# Connector_SOM240_1.net
KiCad netlist of a schematic drawn in Altium Designer
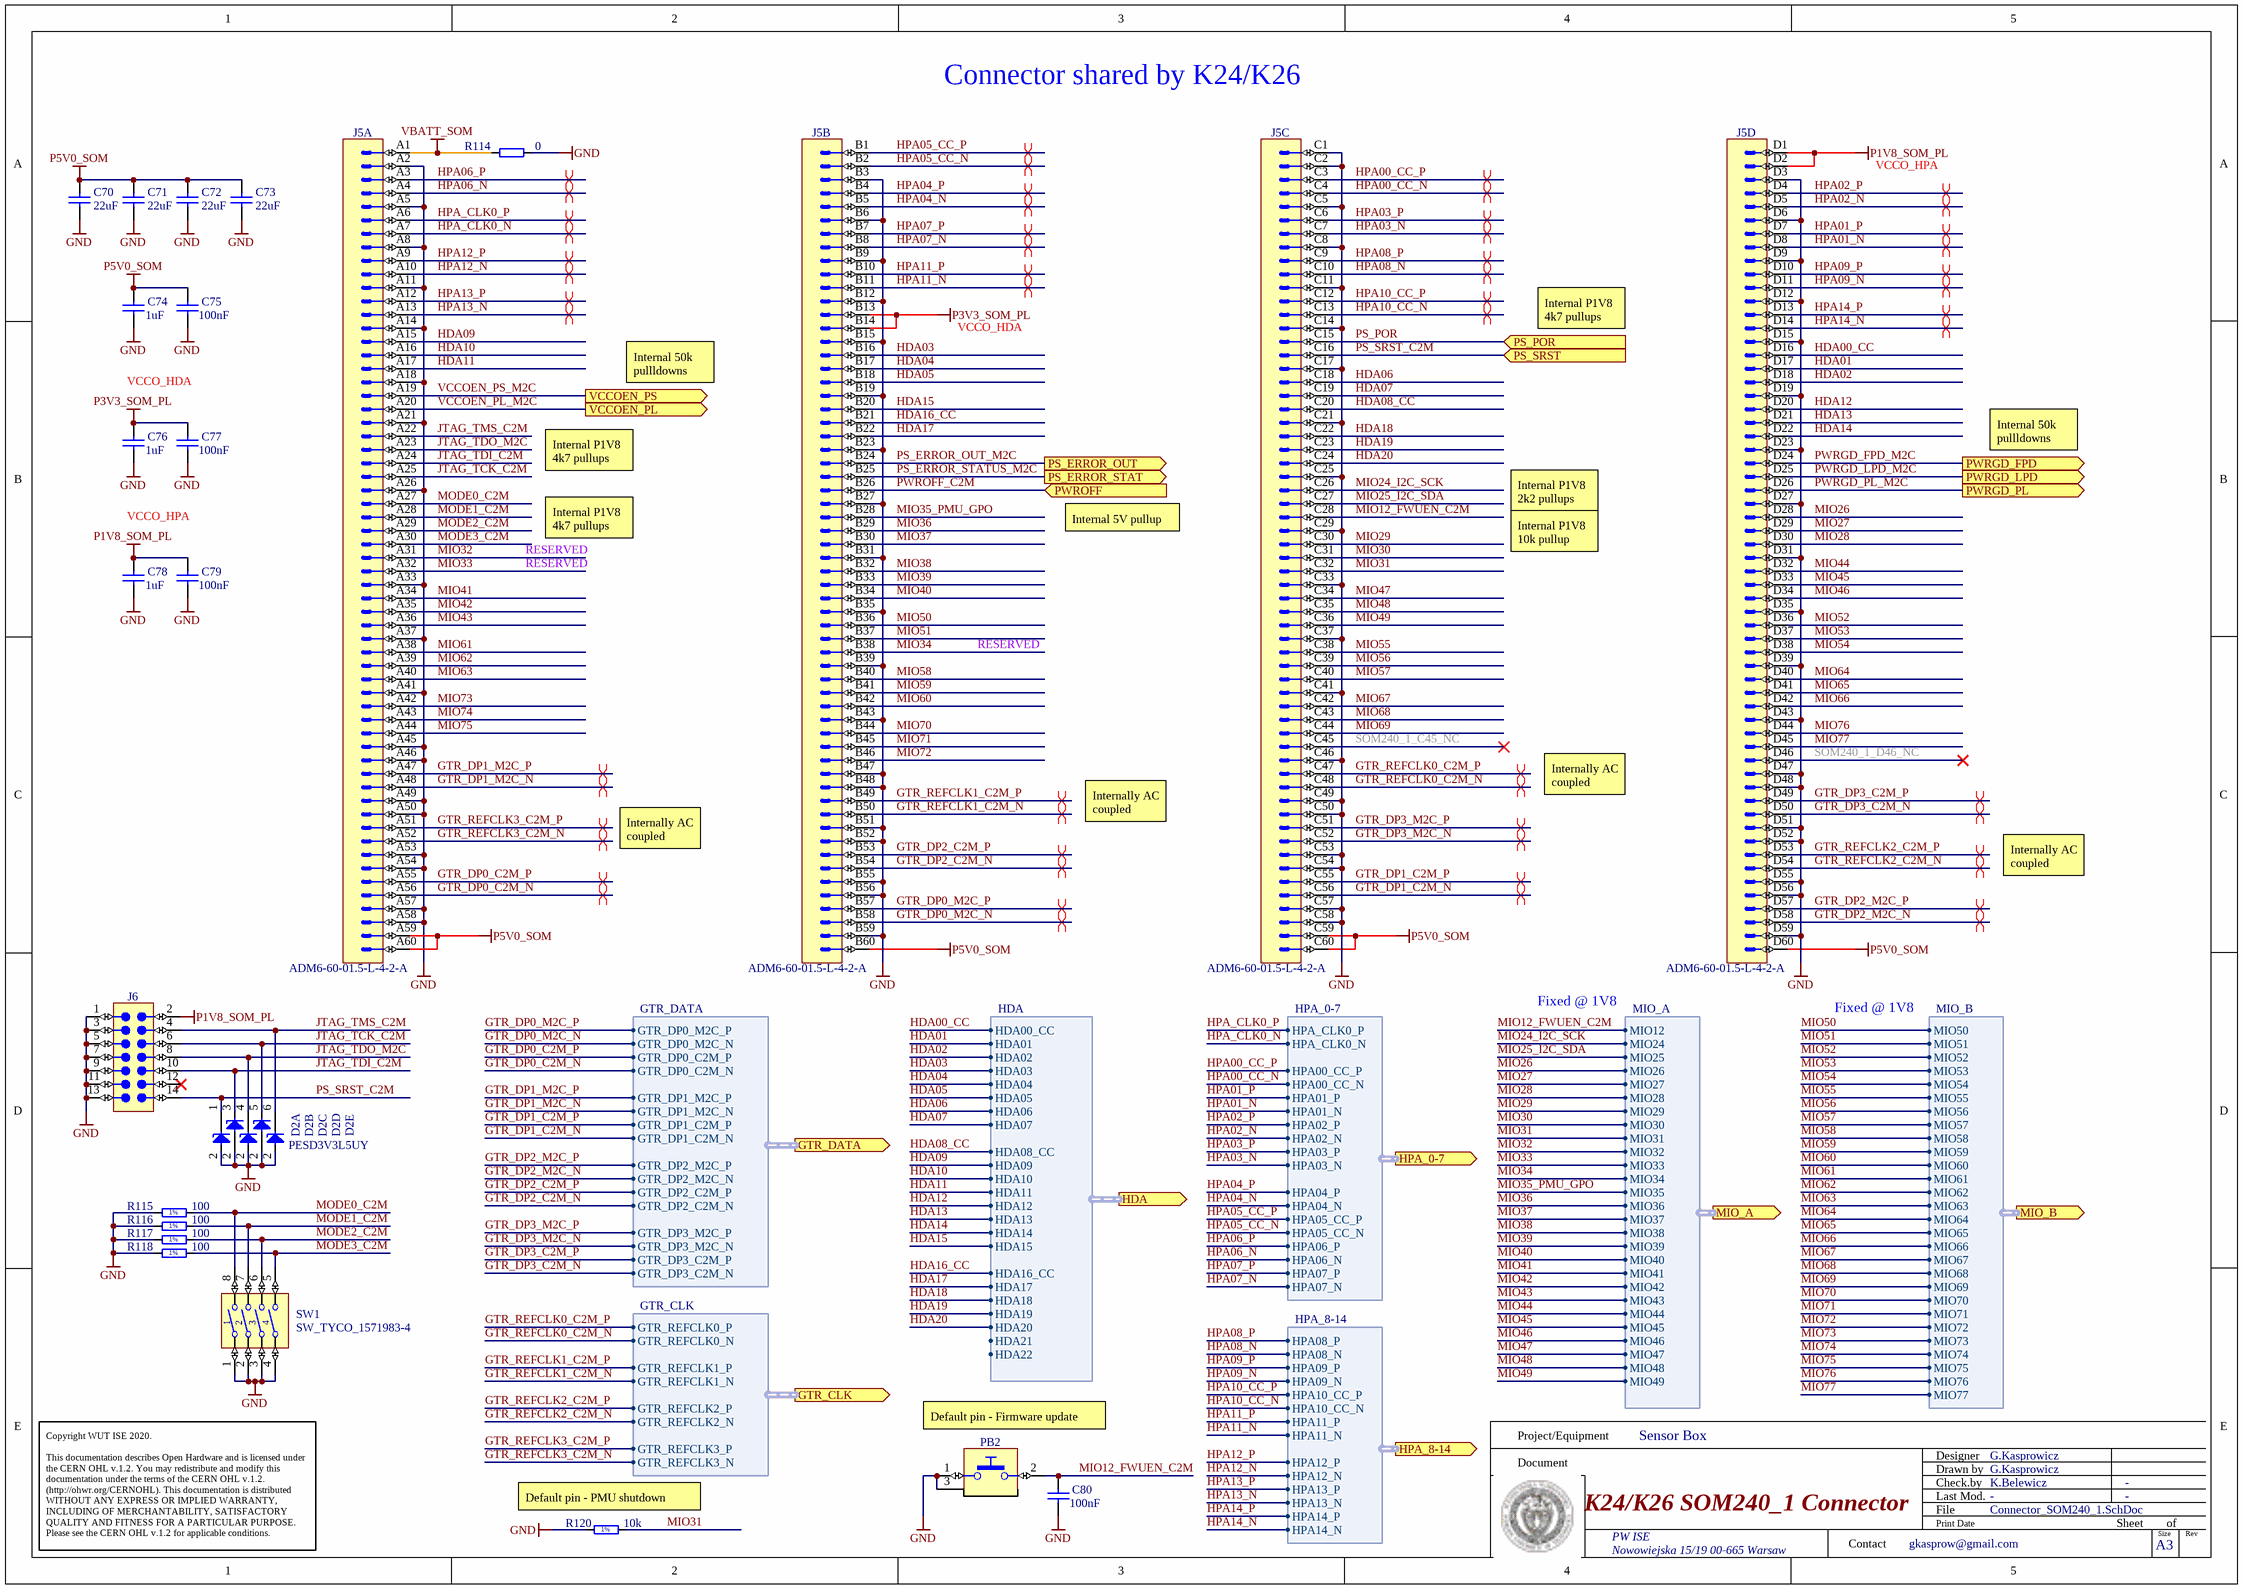
[diagram p0: Connector_SOM240_1.SchDoc]

(export (version "E")
  (design (tool "Eeschema 10.0.6"))
  (components
    (comp (ref "C70")
      (value "22uF")
      (footprint "CAPC2012X135N")
      (description "Non-polarised capacitor")
      (fields
        (field (name "PART NUMBER") "CC0805_22UF_16V_10%_X5R")
        (field (name "VOLTAGE") "16V")
        (field (name "AUTHOR") "CERN DEM JLC")
      )
      (libsource (lib "Capacitors") (part "Capacitor - non polarized"))
    )
    (comp (ref "C71")
      (value "22uF")
      (footprint "CAPC2012X135N")
      (description "Non-polarised capacitor")
      (fields
        (field (name "PART NUMBER") "CC0805_22UF_16V_10%_X5R")
        (field (name "VOLTAGE") "16V")
        (field (name "AUTHOR") "CERN DEM JLC")
      )
      (libsource (lib "Capacitors") (part "Capacitor - non polarized"))
    )
    (comp (ref "C72")
      (value "22uF")
      (footprint "CAPC2012X135N")
      (description "Non-polarised capacitor")
      (fields
        (field (name "PART NUMBER") "CC0805_22UF_16V_10%_X5R")
        (field (name "VOLTAGE") "16V")
        (field (name "AUTHOR") "CERN DEM JLC")
      )
      (libsource (lib "Capacitors") (part "Capacitor - non polarized"))
    )
    (comp (ref "C73")
      (value "22uF")
      (footprint "CAPC2012X135N")
      (description "Non-polarised capacitor")
      (fields
        (field (name "PART NUMBER") "CC0805_22UF_16V_10%_X5R")
        (field (name "VOLTAGE") "16V")
        (field (name "AUTHOR") "CERN DEM JLC")
      )
      (libsource (lib "Capacitors") (part "Capacitor - non polarized"))
    )
    (comp (ref "C74")
      (value "1uF")
      (footprint "CAPC1005X55N")
      (description "Non-polarised capacitor")
      (fields
        (field (name "PART NUMBER") "CC0402_1UF_16V_10%_X5R")
        (field (name "VOLTAGE") "16V")
        (field (name "AUTHOR") "CERN DEM JLC")
      )
      (libsource (lib "Capacitors") (part "Capacitor - non polarized"))
    )
    (comp (ref "C75")
      (value "100nF")
      (footprint "CAPC1005X55N")
      (description "Non-polarised capacitor")
      (fields
        (field (name "PART NUMBER") "CC0402_100NF_16V_10%_X5R")
        (field (name "VOLTAGE") "16V")
        (field (name "AUTHOR") "CERN DEM JLC")
      )
      (libsource (lib "Capacitors") (part "Capacitor - non polarized"))
    )
    (comp (ref "C76")
      (value "1uF")
      (footprint "CAPC1005X55N")
      (description "Non-polarised capacitor")
      (fields
        (field (name "PART NUMBER") "CC0402_1UF_16V_10%_X5R")
        (field (name "VOLTAGE") "16V")
        (field (name "AUTHOR") "CERN DEM JLC")
      )
      (libsource (lib "Capacitors") (part "Capacitor - non polarized"))
    )
    (comp (ref "C77")
      (value "100nF")
      (footprint "CAPC1005X55N")
      (description "Non-polarised capacitor")
      (fields
        (field (name "PART NUMBER") "CC0402_100NF_16V_10%_X5R")
        (field (name "VOLTAGE") "16V")
        (field (name "AUTHOR") "CERN DEM JLC")
      )
      (libsource (lib "Capacitors") (part "Capacitor - non polarized"))
    )
    (comp (ref "C78")
      (value "1uF")
      (footprint "CAPC1005X55N")
      (description "Non-polarised capacitor")
      (fields
        (field (name "PART NUMBER") "CC0402_1UF_16V_10%_X5R")
        (field (name "VOLTAGE") "16V")
        (field (name "AUTHOR") "CERN DEM JLC")
      )
      (libsource (lib "Capacitors") (part "Capacitor - non polarized"))
    )
    (comp (ref "C79")
      (value "100nF")
      (footprint "CAPC1005X55N")
      (description "Non-polarised capacitor")
      (fields
        (field (name "PART NUMBER") "CC0402_100NF_16V_10%_X5R")
        (field (name "VOLTAGE") "16V")
        (field (name "AUTHOR") "CERN DEM JLC")
      )
      (libsource (lib "Capacitors") (part "Capacitor - non polarized"))
    )
    (comp (ref "C80")
      (value "100nF")
      (footprint "CAPC1005X55N")
      (description "Non-polarised capacitor")
      (fields
        (field (name "PART NUMBER") "CC0402_100NF_16V_10%_X5R")
        (field (name "VOLTAGE") "16V")
        (field (name "AUTHOR") "CERN DEM JLC")
      )
      (libsource (lib "Capacitors") (part "Capacitor - non polarized"))
    )
    (comp (ref "D2")
      (value "PESD3V3L5UY")
      (footprint "SOT65P210X110-6N")
      (description "Fivefold ESD Protection Diode Arrays")
      (fields
        (field (name "VOLTAGE") "3.3V")
        (field (name "POWER") "200W")
        (field (name "AUTHOR") "CERN DEM WB")
      )
      (libsource (lib "") (part "PESD Array 5diodes 6pins Common anode2_4"))
    )
    (comp (ref "J5")
      (value "Header 240")
      (footprint "SAMTEC_ADM6-60-01.5-L-4-2-A")
      (description "Connector 240 Male contacts in 4 row abcd")
      (fields
        (field (name "PART NUMBER") "SAMTEC_ADM6-60-01.5-L-4-2-A")
        (field (name "MANUFACTURER") "SAMTEC")
        (field (name "MANUFACTURER PART NUMBER") "ADM6-60-01.5-L-4-2-A")
        (field (name "AUTHOR") "CERN DEM HF")
      )
      (libsource (lib "Connectors") (part "Connector 240 Male (4x60) (abcd)"))
    )
    (comp (ref "J6")
      (value "~")
      (footprint "MOLEX_87832-1420")
      (description "Connector 14 Male")
      (fields
        (field (name "PART NUMBER") "MOLEX_87832-1420")
        (field (name "MANUFACTURER") "MOLEX")
        (field (name "AUTHOR") "CERN DEM JLC")
      )
      (libsource (lib "Connectors") (part "Connector 14 Male"))
    )
    (comp (ref "PB2")
      (value "~")
      (footprint "PB_OMRON_B3U-1100P")
      (description "Push-Button Switch SPDT")
      (fields
        (field (name "PART NUMBER") "PB_OMRON_B3U-1100P")
        (field (name "MANUFACTURER") "OMRON")
        (field (name "AUTHOR") "CERN DEM JLC")
      )
      (libsource (lib "Eletro-mechanical") (part "PB SPST 1NO-2NO 3CASE"))
    )
    (comp (ref "R114")
      (value "0")
      (footprint "RESC1005X40N")
      (description "Resistor")
      (fields
        (field (name "PART NUMBER") "R0402_0R_JUMPER")
        (field (name "MANUFACTURER") "GENERIC")
        (field (name "AUTHOR") "CERN DEM JLC")
      )
      (libsource (lib "Resistors") (part "Resistor"))
    )
    (comp (ref "R115")
      (value "100")
      (footprint "RESC1005X40N")
      (description "Resistor - 1%")
      (fields
        (field (name "PART NUMBER") "R0402_100R_1%_0.0625W_100PPM")
        (field (name "POWER") "0.0625W")
        (field (name "AUTHOR") "CERN DEM JLC")
      )
      (libsource (lib "Resistors") (part "Resistor - 1%"))
    )
    (comp (ref "R116")
      (value "100")
      (footprint "RESC1005X40N")
      (description "Resistor - 1%")
      (fields
        (field (name "PART NUMBER") "R0402_100R_1%_0.0625W_100PPM")
        (field (name "POWER") "0.0625W")
        (field (name "AUTHOR") "CERN DEM JLC")
      )
      (libsource (lib "Resistors") (part "Resistor - 1%"))
    )
    (comp (ref "R117")
      (value "100")
      (footprint "RESC1005X40N")
      (description "Resistor - 1%")
      (fields
        (field (name "PART NUMBER") "R0402_100R_1%_0.0625W_100PPM")
        (field (name "POWER") "0.0625W")
        (field (name "AUTHOR") "CERN DEM JLC")
      )
      (libsource (lib "Resistors") (part "Resistor - 1%"))
    )
    (comp (ref "R118")
      (value "100")
      (footprint "RESC1005X40N")
      (description "Resistor - 1%")
      (fields
        (field (name "PART NUMBER") "R0402_100R_1%_0.0625W_100PPM")
        (field (name "POWER") "0.0625W")
        (field (name "AUTHOR") "CERN DEM JLC")
      )
      (libsource (lib "Resistors") (part "Resistor - 1%"))
    )
    (comp (ref "R120")
      (value "10k")
      (footprint "RESC1005X40N")
      (description "Resistor - 1%")
      (fields
        (field (name "PART NUMBER") "R0402_10K_1%_0.0625W_100PPM")
        (field (name "POWER") "0.0625W")
        (field (name "AUTHOR") "CERN DEM JLC")
      )
      (libsource (lib "Resistors") (part "Resistor - 1%"))
    )
    (comp (ref "SW1")
      (value "Switch")
      (footprint "SW_TYCO_1571983-4")
      (description "4 Ways SPST DIP Switch")
      (fields
        (field (name "PART NUMBER") "SW_TYCO_1571983-4")
        (field (name "MANUFACTURER") "TYCO")
        (field (name "MANUFACTURER PART NUMBER") "1571983-4 or GDH04S04")
        (field (name "AUTHOR") "CERN DEM JLC")
      )
      (libsource (lib "Eletro-mechanical") (part "SW 4x SPST DIP Switch"))
    )
  )
  (nets
    (net (code "8") (name "/GTR_DP0_C2M_N") (class "Default")
      (node (ref "J5") (pin "A56") (pinfunction "A56_A56") (pintype "bidirectional"))
    )
    (net (code "9") (name "/GTR_DP0_C2M_P") (class "Default")
      (node (ref "J5") (pin "A55") (pinfunction "A55_A55") (pintype "bidirectional"))
    )
    (net (code "10") (name "/GTR_DP0_M2C_N") (class "Default")
      (node (ref "J5") (pin "B58") (pinfunction "B58_B58") (pintype "bidirectional"))
    )
    (net (code "11") (name "/GTR_DP0_M2C_P") (class "Default")
      (node (ref "J5") (pin "B57") (pinfunction "B57_B57") (pintype "bidirectional"))
    )
    (net (code "12") (name "/GTR_DP1_C2M_N") (class "Default")
      (node (ref "J5") (pin "C56") (pinfunction "C56_C56") (pintype "bidirectional"))
    )
    (net (code "13") (name "/GTR_DP1_C2M_P") (class "Default")
      (node (ref "J5") (pin "C55") (pinfunction "C55_C55") (pintype "bidirectional"))
    )
    (net (code "14") (name "/GTR_DP1_M2C_N") (class "Default")
      (node (ref "J5") (pin "A48") (pinfunction "A48_A48") (pintype "bidirectional"))
    )
    (net (code "15") (name "/GTR_DP1_M2C_P") (class "Default")
      (node (ref "J5") (pin "A47") (pinfunction "A47_A47") (pintype "bidirectional"))
    )
    (net (code "16") (name "/GTR_DP2_C2M_N") (class "Default")
      (node (ref "J5") (pin "B54") (pinfunction "B54_B54") (pintype "bidirectional"))
    )
    (net (code "17") (name "/GTR_DP2_C2M_P") (class "Default")
      (node (ref "J5") (pin "B53") (pinfunction "B53_B53") (pintype "bidirectional"))
    )
    (net (code "18") (name "/GTR_DP2_M2C_N") (class "Default")
      (node (ref "J5") (pin "D58") (pinfunction "D58_D58") (pintype "bidirectional"))
    )
    (net (code "19") (name "/GTR_DP2_M2C_P") (class "Default")
      (node (ref "J5") (pin "D57") (pinfunction "D57_D57") (pintype "bidirectional"))
    )
    (net (code "20") (name "/GTR_DP3_C2M_N") (class "Default")
      (node (ref "J5") (pin "D50") (pinfunction "D50_D50") (pintype "bidirectional"))
    )
    (net (code "21") (name "/GTR_DP3_C2M_P") (class "Default")
      (node (ref "J5") (pin "D49") (pinfunction "D49_D49") (pintype "bidirectional"))
    )
    (net (code "22") (name "/GTR_DP3_M2C_N") (class "Default")
      (node (ref "J5") (pin "C52") (pinfunction "C52_C52") (pintype "bidirectional"))
    )
    (net (code "23") (name "/GTR_DP3_M2C_P") (class "Default")
      (node (ref "J5") (pin "C51") (pinfunction "C51_C51") (pintype "bidirectional"))
    )
    (net (code "24") (name "/GTR_REFCLK0_C2M_N") (class "Default")
      (node (ref "J5") (pin "C48") (pinfunction "C48_C48") (pintype "bidirectional"))
    )
    (net (code "25") (name "/GTR_REFCLK0_C2M_P") (class "Default")
      (node (ref "J5") (pin "C47") (pinfunction "C47_C47") (pintype "bidirectional"))
    )
    (net (code "26") (name "/GTR_REFCLK1_C2M_N") (class "Default")
      (node (ref "J5") (pin "B50") (pinfunction "B50_B50") (pintype "bidirectional"))
    )
    (net (code "27") (name "/GTR_REFCLK1_C2M_P") (class "Default")
      (node (ref "J5") (pin "B49") (pinfunction "B49_B49") (pintype "bidirectional"))
    )
    (net (code "28") (name "/GTR_REFCLK2_C2M_N") (class "Default")
      (node (ref "J5") (pin "D54") (pinfunction "D54_D54") (pintype "bidirectional"))
    )
    (net (code "29") (name "/GTR_REFCLK2_C2M_P") (class "Default")
      (node (ref "J5") (pin "D53") (pinfunction "D53_D53") (pintype "bidirectional"))
    )
    (net (code "30") (name "/GTR_REFCLK3_C2M_N") (class "Default")
      (node (ref "J5") (pin "A52") (pinfunction "A52_A52") (pintype "bidirectional"))
    )
    (net (code "31") (name "/GTR_REFCLK3_C2M_P") (class "Default")
      (node (ref "J5") (pin "A51") (pinfunction "A51_A51") (pintype "bidirectional"))
    )
    (net (code "32") (name "/HDA00_CC") (class "Default")
      (node (ref "J5") (pin "D16") (pinfunction "D16_D16") (pintype "bidirectional"))
    )
    (net (code "33") (name "/HDA01") (class "Default")
      (node (ref "J5") (pin "D17") (pinfunction "D17_D17") (pintype "bidirectional"))
    )
    (net (code "34") (name "/HDA02") (class "Default")
      (node (ref "J5") (pin "D18") (pinfunction "D18_D18") (pintype "bidirectional"))
    )
    (net (code "35") (name "/HDA03") (class "Default")
      (node (ref "J5") (pin "B16") (pinfunction "B16_B16") (pintype "bidirectional"))
    )
    (net (code "36") (name "/HDA04") (class "Default")
      (node (ref "J5") (pin "B17") (pinfunction "B17_B17") (pintype "bidirectional"))
    )
    (net (code "37") (name "/HDA05") (class "Default")
      (node (ref "J5") (pin "B18") (pinfunction "B18_B18") (pintype "bidirectional"))
    )
    (net (code "38") (name "/HDA06") (class "Default")
      (node (ref "J5") (pin "C18") (pinfunction "C18_C18") (pintype "bidirectional"))
    )
    (net (code "39") (name "/HDA07") (class "Default")
      (node (ref "J5") (pin "C19") (pinfunction "C19_C19") (pintype "bidirectional"))
    )
    (net (code "40") (name "/HDA08_CC") (class "Default")
      (node (ref "J5") (pin "C20") (pinfunction "C20_C20") (pintype "bidirectional"))
    )
    (net (code "41") (name "/HDA09") (class "Default")
      (node (ref "J5") (pin "A15") (pinfunction "A15_A15") (pintype "bidirectional"))
    )
    (net (code "42") (name "/HDA10") (class "Default")
      (node (ref "J5") (pin "A16") (pinfunction "A16_A16") (pintype "bidirectional"))
    )
    (net (code "43") (name "/HDA11") (class "Default")
      (node (ref "J5") (pin "A17") (pinfunction "A17_A17") (pintype "bidirectional"))
    )
    (net (code "44") (name "/HDA12") (class "Default")
      (node (ref "J5") (pin "D20") (pinfunction "D20_D20") (pintype "bidirectional"))
    )
    (net (code "45") (name "/HDA13") (class "Default")
      (node (ref "J5") (pin "D21") (pinfunction "D21_D21") (pintype "bidirectional"))
    )
    (net (code "46") (name "/HDA14") (class "Default")
      (node (ref "J5") (pin "D22") (pinfunction "D22_D22") (pintype "bidirectional"))
    )
    (net (code "47") (name "/HDA15") (class "Default")
      (node (ref "J5") (pin "B20") (pinfunction "B20_B20") (pintype "bidirectional"))
    )
    (net (code "48") (name "/HDA16_CC") (class "Default")
      (node (ref "J5") (pin "B21") (pinfunction "B21_B21") (pintype "bidirectional"))
    )
    (net (code "49") (name "/HDA17") (class "Default")
      (node (ref "J5") (pin "B22") (pinfunction "B22_B22") (pintype "bidirectional"))
    )
    (net (code "50") (name "/HDA18") (class "Default")
      (node (ref "J5") (pin "C22") (pinfunction "C22_C22") (pintype "bidirectional"))
    )
    (net (code "51") (name "/HDA19") (class "Default")
      (node (ref "J5") (pin "C23") (pinfunction "C23_C23") (pintype "bidirectional"))
    )
    (net (code "52") (name "/HDA20") (class "Default")
      (node (ref "J5") (pin "C24") (pinfunction "C24_C24") (pintype "bidirectional"))
    )
    (net (code "53") (name "/HPA00_CC_N") (class "Default")
      (node (ref "J5") (pin "C4") (pinfunction "C4_C4") (pintype "bidirectional"))
    )
    (net (code "54") (name "/HPA00_CC_P") (class "Default")
      (node (ref "J5") (pin "C3") (pinfunction "C3_C3") (pintype "bidirectional"))
    )
    (net (code "55") (name "/HPA01_N") (class "Default")
      (node (ref "J5") (pin "D8") (pinfunction "D8_D8") (pintype "bidirectional"))
    )
    (net (code "56") (name "/HPA01_P") (class "Default")
      (node (ref "J5") (pin "D7") (pinfunction "D7_D7") (pintype "bidirectional"))
    )
    (net (code "57") (name "/HPA02_N") (class "Default")
      (node (ref "J5") (pin "D5") (pinfunction "D5_D5") (pintype "bidirectional"))
    )
    (net (code "58") (name "/HPA02_P") (class "Default")
      (node (ref "J5") (pin "D4") (pinfunction "D4_D4") (pintype "bidirectional"))
    )
    (net (code "59") (name "/HPA03_N") (class "Default")
      (node (ref "J5") (pin "C7") (pinfunction "C7_C7") (pintype "bidirectional"))
    )
    (net (code "60") (name "/HPA03_P") (class "Default")
      (node (ref "J5") (pin "C6") (pinfunction "C6_C6") (pintype "bidirectional"))
    )
    (net (code "61") (name "/HPA04_N") (class "Default")
      (node (ref "J5") (pin "B5") (pinfunction "B5_B5") (pintype "bidirectional"))
    )
    (net (code "62") (name "/HPA04_P") (class "Default")
      (node (ref "J5") (pin "B4") (pinfunction "B4_B4") (pintype "bidirectional"))
    )
    (net (code "63") (name "/HPA05_CC_N") (class "Default")
      (node (ref "J5") (pin "B2") (pinfunction "B2_B2") (pintype "bidirectional"))
    )
    (net (code "64") (name "/HPA05_CC_P") (class "Default")
      (node (ref "J5") (pin "B1") (pinfunction "B1_B1") (pintype "bidirectional"))
    )
    (net (code "65") (name "/HPA06_N") (class "Default")
      (node (ref "J5") (pin "A4") (pinfunction "A4_A4") (pintype "bidirectional"))
    )
    (net (code "66") (name "/HPA06_P") (class "Default")
      (node (ref "J5") (pin "A3") (pinfunction "A3_A3") (pintype "bidirectional"))
    )
    (net (code "67") (name "/HPA07_N") (class "Default")
      (node (ref "J5") (pin "B8") (pinfunction "B8_B8") (pintype "bidirectional"))
    )
    (net (code "68") (name "/HPA07_P") (class "Default")
      (node (ref "J5") (pin "B7") (pinfunction "B7_B7") (pintype "bidirectional"))
    )
    (net (code "69") (name "/HPA08_N") (class "Default")
      (node (ref "J5") (pin "C10") (pinfunction "C10_C10") (pintype "bidirectional"))
    )
    (net (code "70") (name "/HPA08_P") (class "Default")
      (node (ref "J5") (pin "C9") (pinfunction "C9_C9") (pintype "bidirectional"))
    )
    (net (code "71") (name "/HPA09_N") (class "Default")
      (node (ref "J5") (pin "D11") (pinfunction "D11_D11") (pintype "bidirectional"))
    )
    (net (code "72") (name "/HPA09_P") (class "Default")
      (node (ref "J5") (pin "D10") (pinfunction "D10_D10") (pintype "bidirectional"))
    )
    (net (code "73") (name "/HPA10_CC_N") (class "Default")
      (node (ref "J5") (pin "C13") (pinfunction "C13_C13") (pintype "bidirectional"))
    )
    (net (code "74") (name "/HPA10_CC_P") (class "Default")
      (node (ref "J5") (pin "C12") (pinfunction "C12_C12") (pintype "bidirectional"))
    )
    (net (code "75") (name "/HPA11_N") (class "Default")
      (node (ref "J5") (pin "B11") (pinfunction "B11_B11") (pintype "bidirectional"))
    )
    (net (code "76") (name "/HPA11_P") (class "Default")
      (node (ref "J5") (pin "B10") (pinfunction "B10_B10") (pintype "bidirectional"))
    )
    (net (code "77") (name "/HPA12_N") (class "Default")
      (node (ref "J5") (pin "A10") (pinfunction "A10_A10") (pintype "bidirectional"))
    )
    (net (code "78") (name "/HPA12_P") (class "Default")
      (node (ref "J5") (pin "A9") (pinfunction "A9_A9") (pintype "bidirectional"))
    )
    (net (code "79") (name "/HPA13_N") (class "Default")
      (node (ref "J5") (pin "A13") (pinfunction "A13_A13") (pintype "bidirectional"))
    )
    (net (code "80") (name "/HPA13_P") (class "Default")
      (node (ref "J5") (pin "A12") (pinfunction "A12_A12") (pintype "bidirectional"))
    )
    (net (code "81") (name "/HPA14_N") (class "Default")
      (node (ref "J5") (pin "D14") (pinfunction "D14_D14") (pintype "bidirectional"))
    )
    (net (code "82") (name "/HPA14_P") (class "Default")
      (node (ref "J5") (pin "D13") (pinfunction "D13_D13") (pintype "bidirectional"))
    )
    (net (code "83") (name "/HPA_CLK0_N") (class "Default")
      (node (ref "J5") (pin "A7") (pinfunction "A7_A7") (pintype "bidirectional"))
    )
    (net (code "84") (name "/HPA_CLK0_P") (class "Default")
      (node (ref "J5") (pin "A6") (pinfunction "A6_A6") (pintype "bidirectional"))
    )
    (net (code "85") (name "/JTAG_TCK_C2M") (class "Default")
      (node (ref "D2") (pin "5") (pinfunction "C_5") (pintype "passive"))
      (node (ref "J5") (pin "A25") (pinfunction "A25_A25") (pintype "bidirectional"))
      (node (ref "J6") (pin "6") (pinfunction "6_6") (pintype "bidirectional"))
    )
    (net (code "86") (name "/JTAG_TDI_C2M") (class "Default")
      (node (ref "D2") (pin "3") (pinfunction "C_3") (pintype "passive"))
      (node (ref "J5") (pin "A24") (pinfunction "A24_A24") (pintype "bidirectional"))
      (node (ref "J6") (pin "10") (pinfunction "10_10") (pintype "bidirectional"))
    )
    (net (code "87") (name "/JTAG_TDO_M2C") (class "Default")
      (node (ref "D2") (pin "4") (pinfunction "C_4") (pintype "passive"))
      (node (ref "J5") (pin "A23") (pinfunction "A23_A23") (pintype "bidirectional"))
      (node (ref "J6") (pin "8") (pinfunction "8_8") (pintype "bidirectional"))
    )
    (net (code "88") (name "/JTAG_TMS_C2M") (class "Default")
      (node (ref "D2") (pin "6") (pinfunction "C_6") (pintype "passive"))
      (node (ref "J5") (pin "A22") (pinfunction "A22_A22") (pintype "bidirectional"))
      (node (ref "J6") (pin "4") (pinfunction "4_4") (pintype "bidirectional"))
    )
    (net (code "89") (name "/MIO12_FWUEN_C2M") (class "Default")
      (node (ref "C80") (pin "2") (pinfunction "2_2") (pintype "passive"))
      (node (ref "J5") (pin "C28") (pinfunction "C28_C28") (pintype "bidirectional"))
      (node (ref "PB2") (pin "2") (pinfunction "2_2") (pintype "bidirectional"))
    )
    (net (code "90") (name "/MIO24_I2C_SCK") (class "Default")
      (node (ref "J5") (pin "C26") (pinfunction "C26_C26") (pintype "bidirectional"))
    )
    (net (code "91") (name "/MIO25_I2C_SDA") (class "Default")
      (node (ref "J5") (pin "C27") (pinfunction "C27_C27") (pintype "bidirectional"))
    )
    (net (code "92") (name "/MIO26") (class "Default")
      (node (ref "J5") (pin "D28") (pinfunction "D28_D28") (pintype "bidirectional"))
    )
    (net (code "93") (name "/MIO27") (class "Default")
      (node (ref "J5") (pin "D29") (pinfunction "D29_D29") (pintype "bidirectional"))
    )
    (net (code "94") (name "/MIO28") (class "Default")
      (node (ref "J5") (pin "D30") (pinfunction "D30_D30") (pintype "bidirectional"))
    )
    (net (code "95") (name "/MIO29") (class "Default")
      (node (ref "J5") (pin "C30") (pinfunction "C30_C30") (pintype "bidirectional"))
    )
    (net (code "96") (name "/MIO30") (class "Default")
      (node (ref "J5") (pin "C31") (pinfunction "C31_C31") (pintype "bidirectional"))
    )
    (net (code "97") (name "/MIO31") (class "Default")
      (node (ref "J5") (pin "C32") (pinfunction "C32_C32") (pintype "bidirectional"))
      (node (ref "R120") (pin "2") (pinfunction "2_2") (pintype "passive"))
    )
    (net (code "98") (name "/MIO32") (class "Default")
      (node (ref "J5") (pin "A31") (pinfunction "A31_A31") (pintype "bidirectional"))
    )
    (net (code "99") (name "/MIO33") (class "Default")
      (node (ref "J5") (pin "A32") (pinfunction "A32_A32") (pintype "bidirectional"))
    )
    (net (code "100") (name "/MIO34") (class "Default")
      (node (ref "J5") (pin "B38") (pinfunction "B38_B38") (pintype "bidirectional"))
    )
    (net (code "101") (name "/MIO35_PMU_GPO") (class "Default")
      (node (ref "J5") (pin "B28") (pinfunction "B28_B28") (pintype "bidirectional"))
    )
    (net (code "102") (name "/MIO36") (class "Default")
      (node (ref "J5") (pin "B29") (pinfunction "B29_B29") (pintype "bidirectional"))
    )
    (net (code "103") (name "/MIO37") (class "Default")
      (node (ref "J5") (pin "B30") (pinfunction "B30_B30") (pintype "bidirectional"))
    )
    (net (code "104") (name "/MIO38") (class "Default")
      (node (ref "J5") (pin "B32") (pinfunction "B32_B32") (pintype "bidirectional"))
    )
    (net (code "105") (name "/MIO39") (class "Default")
      (node (ref "J5") (pin "B33") (pinfunction "B33_B33") (pintype "bidirectional"))
    )
    (net (code "106") (name "/MIO40") (class "Default")
      (node (ref "J5") (pin "B34") (pinfunction "B34_B34") (pintype "bidirectional"))
    )
    (net (code "107") (name "/MIO41") (class "Default")
      (node (ref "J5") (pin "A34") (pinfunction "A34_A34") (pintype "bidirectional"))
    )
    (net (code "108") (name "/MIO42") (class "Default")
      (node (ref "J5") (pin "A35") (pinfunction "A35_A35") (pintype "bidirectional"))
    )
    (net (code "109") (name "/MIO43") (class "Default")
      (node (ref "J5") (pin "A36") (pinfunction "A36_A36") (pintype "bidirectional"))
    )
    (net (code "110") (name "/MIO44") (class "Default")
      (node (ref "J5") (pin "D32") (pinfunction "D32_D32") (pintype "bidirectional"))
    )
    (net (code "111") (name "/MIO45") (class "Default")
      (node (ref "J5") (pin "D33") (pinfunction "D33_D33") (pintype "bidirectional"))
    )
    (net (code "112") (name "/MIO46") (class "Default")
      (node (ref "J5") (pin "D34") (pinfunction "D34_D34") (pintype "bidirectional"))
    )
    (net (code "113") (name "/MIO47") (class "Default")
      (node (ref "J5") (pin "C34") (pinfunction "C34_C34") (pintype "bidirectional"))
    )
    (net (code "114") (name "/MIO48") (class "Default")
      (node (ref "J5") (pin "C35") (pinfunction "C35_C35") (pintype "bidirectional"))
    )
    (net (code "115") (name "/MIO49") (class "Default")
      (node (ref "J5") (pin "C36") (pinfunction "C36_C36") (pintype "bidirectional"))
    )
    (net (code "116") (name "/MIO50") (class "Default")
      (node (ref "J5") (pin "B36") (pinfunction "B36_B36") (pintype "bidirectional"))
    )
    (net (code "117") (name "/MIO51") (class "Default")
      (node (ref "J5") (pin "B37") (pinfunction "B37_B37") (pintype "bidirectional"))
    )
    (net (code "118") (name "/MIO52") (class "Default")
      (node (ref "J5") (pin "D36") (pinfunction "D36_D36") (pintype "bidirectional"))
    )
    (net (code "119") (name "/MIO53") (class "Default")
      (node (ref "J5") (pin "D37") (pinfunction "D37_D37") (pintype "bidirectional"))
    )
    (net (code "120") (name "/MIO54") (class "Default")
      (node (ref "J5") (pin "D38") (pinfunction "D38_D38") (pintype "bidirectional"))
    )
    (net (code "121") (name "/MIO55") (class "Default")
      (node (ref "J5") (pin "C38") (pinfunction "C38_C38") (pintype "bidirectional"))
    )
    (net (code "122") (name "/MIO56") (class "Default")
      (node (ref "J5") (pin "C39") (pinfunction "C39_C39") (pintype "bidirectional"))
    )
    (net (code "123") (name "/MIO57") (class "Default")
      (node (ref "J5") (pin "C40") (pinfunction "C40_C40") (pintype "bidirectional"))
    )
    (net (code "124") (name "/MIO58") (class "Default")
      (node (ref "J5") (pin "B40") (pinfunction "B40_B40") (pintype "bidirectional"))
    )
    (net (code "125") (name "/MIO59") (class "Default")
      (node (ref "J5") (pin "B41") (pinfunction "B41_B41") (pintype "bidirectional"))
    )
    (net (code "126") (name "/MIO60") (class "Default")
      (node (ref "J5") (pin "B42") (pinfunction "B42_B42") (pintype "bidirectional"))
    )
    (net (code "127") (name "/MIO61") (class "Default")
      (node (ref "J5") (pin "A38") (pinfunction "A38_A38") (pintype "bidirectional"))
    )
    (net (code "128") (name "/MIO62") (class "Default")
      (node (ref "J5") (pin "A39") (pinfunction "A39_A39") (pintype "bidirectional"))
    )
    (net (code "129") (name "/MIO63") (class "Default")
      (node (ref "J5") (pin "A40") (pinfunction "A40_A40") (pintype "bidirectional"))
    )
    (net (code "130") (name "/MIO64") (class "Default")
      (node (ref "J5") (pin "D40") (pinfunction "D40_D40") (pintype "bidirectional"))
    )
    (net (code "131") (name "/MIO65") (class "Default")
      (node (ref "J5") (pin "D41") (pinfunction "D41_D41") (pintype "bidirectional"))
    )
    (net (code "132") (name "/MIO66") (class "Default")
      (node (ref "J5") (pin "D42") (pinfunction "D42_D42") (pintype "bidirectional"))
    )
    (net (code "133") (name "/MIO67") (class "Default")
      (node (ref "J5") (pin "C42") (pinfunction "C42_C42") (pintype "bidirectional"))
    )
    (net (code "134") (name "/MIO68") (class "Default")
      (node (ref "J5") (pin "C43") (pinfunction "C43_C43") (pintype "bidirectional"))
    )
    (net (code "135") (name "/MIO69") (class "Default")
      (node (ref "J5") (pin "C44") (pinfunction "C44_C44") (pintype "bidirectional"))
    )
    (net (code "136") (name "/MIO70") (class "Default")
      (node (ref "J5") (pin "B44") (pinfunction "B44_B44") (pintype "bidirectional"))
    )
    (net (code "137") (name "/MIO71") (class "Default")
      (node (ref "J5") (pin "B45") (pinfunction "B45_B45") (pintype "bidirectional"))
    )
    (net (code "138") (name "/MIO72") (class "Default")
      (node (ref "J5") (pin "B46") (pinfunction "B46_B46") (pintype "bidirectional"))
    )
    (net (code "139") (name "/MIO73") (class "Default")
      (node (ref "J5") (pin "A42") (pinfunction "A42_A42") (pintype "bidirectional"))
    )
    (net (code "140") (name "/MIO74") (class "Default")
      (node (ref "J5") (pin "A43") (pinfunction "A43_A43") (pintype "bidirectional"))
    )
    (net (code "141") (name "/MIO75") (class "Default")
      (node (ref "J5") (pin "A44") (pinfunction "A44_A44") (pintype "bidirectional"))
    )
    (net (code "142") (name "/MIO76") (class "Default")
      (node (ref "J5") (pin "D44") (pinfunction "D44_D44") (pintype "bidirectional"))
    )
    (net (code "143") (name "/MIO77") (class "Default")
      (node (ref "J5") (pin "D45") (pinfunction "D45_D45") (pintype "bidirectional"))
    )
    (net (code "144") (name "/MODE0_C2M") (class "Default")
      (node (ref "J5") (pin "A27") (pinfunction "A27_A27") (pintype "bidirectional"))
      (node (ref "R115") (pin "2") (pinfunction "2_2") (pintype "passive"))
      (node (ref "SW1") (pin "8") (pinfunction "8_8") (pintype "bidirectional"))
    )
    (net (code "145") (name "/MODE1_C2M") (class "Default")
      (node (ref "J5") (pin "A28") (pinfunction "A28_A28") (pintype "bidirectional"))
      (node (ref "R116") (pin "2") (pinfunction "2_2") (pintype "passive"))
      (node (ref "SW1") (pin "7") (pinfunction "7_7") (pintype "bidirectional"))
    )
    (net (code "146") (name "/MODE2_C2M") (class "Default")
      (node (ref "J5") (pin "A29") (pinfunction "A29_A29") (pintype "bidirectional"))
      (node (ref "R117") (pin "2") (pinfunction "2_2") (pintype "passive"))
      (node (ref "SW1") (pin "6") (pinfunction "6_6") (pintype "bidirectional"))
    )
    (net (code "147") (name "/MODE3_C2M") (class "Default")
      (node (ref "J5") (pin "A30") (pinfunction "A30_A30") (pintype "bidirectional"))
      (node (ref "R118") (pin "2") (pinfunction "2_2") (pintype "passive"))
      (node (ref "SW1") (pin "5") (pinfunction "5_5") (pintype "bidirectional"))
    )
    (net (code "148") (name "/PS_ERROR_OUT_M2C") (class "Default")
      (node (ref "J5") (pin "B24") (pinfunction "B24_B24") (pintype "bidirectional"))
    )
    (net (code "149") (name "/PS_ERROR_STATUS_M2C") (class "Default")
      (node (ref "J5") (pin "B25") (pinfunction "B25_B25") (pintype "bidirectional"))
    )
    (net (code "150") (name "/PS_POR") (class "Default")
      (node (ref "J5") (pin "C15") (pinfunction "C15_C15") (pintype "bidirectional"))
    )
    (net (code "151") (name "/PS_SRST_C2M") (class "Default")
      (node (ref "D2") (pin "1") (pinfunction "C_1") (pintype "passive"))
      (node (ref "J5") (pin "C16") (pinfunction "C16_C16") (pintype "bidirectional"))
      (node (ref "J6") (pin "14") (pinfunction "14_14") (pintype "bidirectional"))
    )
    (net (code "152") (name "/PWRGD_FPD_M2C") (class "Default")
      (node (ref "J5") (pin "D24") (pinfunction "D24_D24") (pintype "bidirectional"))
    )
    (net (code "153") (name "/PWRGD_LPD_M2C") (class "Default")
      (node (ref "J5") (pin "D25") (pinfunction "D25_D25") (pintype "bidirectional"))
    )
    (net (code "154") (name "/PWRGD_PL_M2C") (class "Default")
      (node (ref "J5") (pin "D26") (pinfunction "D26_D26") (pintype "bidirectional"))
    )
    (net (code "155") (name "/PWROFF_C2M") (class "Default")
      (node (ref "J5") (pin "B26") (pinfunction "B26_B26") (pintype "bidirectional"))
    )
    (net (code "156") (name "/SOM240_1_C45_NC") (class "Default")
      (node (ref "J5") (pin "C45") (pinfunction "C45_C45") (pintype "bidirectional+no_connect"))
    )
    (net (code "157") (name "/SOM240_1_D46_NC") (class "Default")
      (node (ref "J5") (pin "D46") (pinfunction "D46_D46") (pintype "bidirectional+no_connect"))
    )
    (net (code "158") (name "/VCCOEN_PL_M2C") (class "Default")
      (node (ref "J5") (pin "A20") (pinfunction "A20_A20") (pintype "bidirectional"))
    )
    (net (code "159") (name "/VCCOEN_PS_M2C") (class "Default")
      (node (ref "J5") (pin "A19") (pinfunction "A19_A19") (pintype "bidirectional"))
    )
    (net (code "167") (name "GND") (class "Default")
      (node (ref "C70") (pin "1") (pinfunction "1_1") (pintype "passive"))
      (node (ref "C71") (pin "1") (pinfunction "1_1") (pintype "passive"))
      (node (ref "C72") (pin "1") (pinfunction "1_1") (pintype "passive"))
      (node (ref "C73") (pin "1") (pinfunction "1_1") (pintype "passive"))
      (node (ref "C74") (pin "1") (pinfunction "1_1") (pintype "passive"))
      (node (ref "C75") (pin "1") (pinfunction "1_1") (pintype "passive"))
      (node (ref "C76") (pin "1") (pinfunction "1_1") (pintype "passive"))
      (node (ref "C77") (pin "1") (pinfunction "1_1") (pintype "passive"))
      (node (ref "C78") (pin "1") (pinfunction "1_1") (pintype "passive"))
      (node (ref "C79") (pin "1") (pinfunction "1_1") (pintype "passive"))
      (node (ref "C80") (pin "1") (pinfunction "1_1") (pintype "passive"))
      (node (ref "D2") (pin "2") (pinfunction "A_2") (pintype "passive"))
      (node (ref "J5") (pin "A11") (pinfunction "A11_A11") (pintype "bidirectional"))
      (node (ref "J5") (pin "A14") (pinfunction "A14_A14") (pintype "bidirectional"))
      (node (ref "J5") (pin "A18") (pinfunction "A18_A18") (pintype "bidirectional"))
      (node (ref "J5") (pin "A2") (pinfunction "A2_A2") (pintype "bidirectional"))
      (node (ref "J5") (pin "A21") (pinfunction "A21_A21") (pintype "bidirectional"))
      (node (ref "J5") (pin "A26") (pinfunction "A26_A26") (pintype "bidirectional"))
      (node (ref "J5") (pin "A33") (pinfunction "A33_A33") (pintype "bidirectional"))
      (node (ref "J5") (pin "A37") (pinfunction "A37_A37") (pintype "bidirectional"))
      (node (ref "J5") (pin "A41") (pinfunction "A41_A41") (pintype "bidirectional"))
      (node (ref "J5") (pin "A45") (pinfunction "A45_A45") (pintype "bidirectional"))
      (node (ref "J5") (pin "A46") (pinfunction "A46_A46") (pintype "bidirectional"))
      (node (ref "J5") (pin "A49") (pinfunction "A49_A49") (pintype "bidirectional"))
      (node (ref "J5") (pin "A5") (pinfunction "A5_A5") (pintype "bidirectional"))
      (node (ref "J5") (pin "A50") (pinfunction "A50_A50") (pintype "bidirectional"))
      (node (ref "J5") (pin "A53") (pinfunction "A53_A53") (pintype "bidirectional"))
      (node (ref "J5") (pin "A54") (pinfunction "A54_A54") (pintype "bidirectional"))
      (node (ref "J5") (pin "A57") (pinfunction "A57_A57") (pintype "bidirectional"))
      (node (ref "J5") (pin "A58") (pinfunction "A58_A58") (pintype "bidirectional"))
      (node (ref "J5") (pin "A8") (pinfunction "A8_A8") (pintype "bidirectional"))
      (node (ref "J5") (pin "B12") (pinfunction "B12_B12") (pintype "bidirectional"))
      (node (ref "J5") (pin "B15") (pinfunction "B15_B15") (pintype "bidirectional"))
      (node (ref "J5") (pin "B19") (pinfunction "B19_B19") (pintype "bidirectional"))
      (node (ref "J5") (pin "B23") (pinfunction "B23_B23") (pintype "bidirectional"))
      (node (ref "J5") (pin "B27") (pinfunction "B27_B27") (pintype "bidirectional"))
      (node (ref "J5") (pin "B3") (pinfunction "B3_B3") (pintype "bidirectional"))
      (node (ref "J5") (pin "B31") (pinfunction "B31_B31") (pintype "bidirectional"))
      (node (ref "J5") (pin "B35") (pinfunction "B35_B35") (pintype "bidirectional"))
      (node (ref "J5") (pin "B39") (pinfunction "B39_B39") (pintype "bidirectional"))
      (node (ref "J5") (pin "B43") (pinfunction "B43_B43") (pintype "bidirectional"))
      (node (ref "J5") (pin "B47") (pinfunction "B47_B47") (pintype "bidirectional"))
      (node (ref "J5") (pin "B48") (pinfunction "B48_B48") (pintype "bidirectional"))
      (node (ref "J5") (pin "B51") (pinfunction "B51_B51") (pintype "bidirectional"))
      (node (ref "J5") (pin "B52") (pinfunction "B52_B52") (pintype "bidirectional"))
      (node (ref "J5") (pin "B55") (pinfunction "B55_B55") (pintype "bidirectional"))
      (node (ref "J5") (pin "B56") (pinfunction "B56_B56") (pintype "bidirectional"))
      (node (ref "J5") (pin "B59") (pinfunction "B59_B59") (pintype "bidirectional"))
      (node (ref "J5") (pin "B6") (pinfunction "B6_B6") (pintype "bidirectional"))
      (node (ref "J5") (pin "B9") (pinfunction "B9_B9") (pintype "bidirectional"))
      (node (ref "J5") (pin "C1") (pinfunction "C1_C1") (pintype "bidirectional"))
      (node (ref "J5") (pin "C11") (pinfunction "C11_C11") (pintype "bidirectional"))
      (node (ref "J5") (pin "C14") (pinfunction "C14_C14") (pintype "bidirectional"))
      (node (ref "J5") (pin "C17") (pinfunction "C17_C17") (pintype "bidirectional"))
      (node (ref "J5") (pin "C2") (pinfunction "C2_C2") (pintype "bidirectional"))
      (node (ref "J5") (pin "C21") (pinfunction "C21_C21") (pintype "bidirectional"))
      (node (ref "J5") (pin "C25") (pinfunction "C25_C25") (pintype "bidirectional"))
      (node (ref "J5") (pin "C29") (pinfunction "C29_C29") (pintype "bidirectional"))
      (node (ref "J5") (pin "C33") (pinfunction "C33_C33") (pintype "bidirectional"))
      (node (ref "J5") (pin "C37") (pinfunction "C37_C37") (pintype "bidirectional"))
      (node (ref "J5") (pin "C41") (pinfunction "C41_C41") (pintype "bidirectional"))
      (node (ref "J5") (pin "C46") (pinfunction "C46_C46") (pintype "bidirectional"))
      (node (ref "J5") (pin "C49") (pinfunction "C49_C49") (pintype "bidirectional"))
      (node (ref "J5") (pin "C5") (pinfunction "C5_C5") (pintype "bidirectional"))
      (node (ref "J5") (pin "C50") (pinfunction "C50_C50") (pintype "bidirectional"))
      (node (ref "J5") (pin "C53") (pinfunction "C53_C53") (pintype "bidirectional"))
      (node (ref "J5") (pin "C54") (pinfunction "C54_C54") (pintype "bidirectional"))
      (node (ref "J5") (pin "C57") (pinfunction "C57_C57") (pintype "bidirectional"))
      (node (ref "J5") (pin "C58") (pinfunction "C58_C58") (pintype "bidirectional"))
      (node (ref "J5") (pin "C8") (pinfunction "C8_C8") (pintype "bidirectional"))
      (node (ref "J5") (pin "D12") (pinfunction "D12_D12") (pintype "bidirectional"))
      (node (ref "J5") (pin "D15") (pinfunction "D15_D15") (pintype "bidirectional"))
      (node (ref "J5") (pin "D19") (pinfunction "D19_D19") (pintype "bidirectional"))
      (node (ref "J5") (pin "D23") (pinfunction "D23_D23") (pintype "bidirectional"))
      (node (ref "J5") (pin "D27") (pinfunction "D27_D27") (pintype "bidirectional"))
      (node (ref "J5") (pin "D3") (pinfunction "D3_D3") (pintype "bidirectional"))
      (node (ref "J5") (pin "D31") (pinfunction "D31_D31") (pintype "bidirectional"))
      (node (ref "J5") (pin "D35") (pinfunction "D35_D35") (pintype "bidirectional"))
      (node (ref "J5") (pin "D39") (pinfunction "D39_D39") (pintype "bidirectional"))
      (node (ref "J5") (pin "D43") (pinfunction "D43_D43") (pintype "bidirectional"))
      (node (ref "J5") (pin "D47") (pinfunction "D47_D47") (pintype "bidirectional"))
      (node (ref "J5") (pin "D48") (pinfunction "D48_D48") (pintype "bidirectional"))
      (node (ref "J5") (pin "D51") (pinfunction "D51_D51") (pintype "bidirectional"))
      (node (ref "J5") (pin "D52") (pinfunction "D52_D52") (pintype "bidirectional"))
      (node (ref "J5") (pin "D55") (pinfunction "D55_D55") (pintype "bidirectional"))
      (node (ref "J5") (pin "D56") (pinfunction "D56_D56") (pintype "bidirectional"))
      (node (ref "J5") (pin "D59") (pinfunction "D59_D59") (pintype "bidirectional"))
      (node (ref "J5") (pin "D6") (pinfunction "D6_D6") (pintype "bidirectional"))
      (node (ref "J5") (pin "D9") (pinfunction "D9_D9") (pintype "bidirectional"))
      (node (ref "J6") (pin "1") (pinfunction "1_1") (pintype "bidirectional"))
      (node (ref "J6") (pin "11") (pinfunction "11_11") (pintype "bidirectional"))
      (node (ref "J6") (pin "13") (pinfunction "13_13") (pintype "bidirectional"))
      (node (ref "J6") (pin "3") (pinfunction "3_3") (pintype "bidirectional"))
      (node (ref "J6") (pin "5") (pinfunction "5_5") (pintype "bidirectional"))
      (node (ref "J6") (pin "7") (pinfunction "7_7") (pintype "bidirectional"))
      (node (ref "J6") (pin "9") (pinfunction "9_9") (pintype "bidirectional"))
      (node (ref "PB2") (pin "1") (pinfunction "1_1") (pintype "bidirectional"))
      (node (ref "PB2") (pin "3") (pinfunction "3_3") (pintype "passive"))
      (node (ref "R114") (pin "2") (pinfunction "2_2") (pintype "passive"))
      (node (ref "R115") (pin "1") (pinfunction "1_1") (pintype "passive"))
      (node (ref "R116") (pin "1") (pinfunction "1_1") (pintype "passive"))
      (node (ref "R117") (pin "1") (pinfunction "1_1") (pintype "passive"))
      (node (ref "R118") (pin "1") (pinfunction "1_1") (pintype "passive"))
      (node (ref "R120") (pin "1") (pinfunction "1_1") (pintype "passive"))
      (node (ref "SW1") (pin "1") (pinfunction "1_1") (pintype "bidirectional"))
      (node (ref "SW1") (pin "2") (pinfunction "2_2") (pintype "bidirectional"))
      (node (ref "SW1") (pin "3") (pinfunction "3_3") (pintype "bidirectional"))
      (node (ref "SW1") (pin "4") (pinfunction "4_4") (pintype "bidirectional"))
    )
    (net (code "168") (name "P1V8_SOM_PL") (class "Default")
      (node (ref "C78") (pin "2") (pinfunction "2_2") (pintype "passive"))
      (node (ref "C79") (pin "2") (pinfunction "2_2") (pintype "passive"))
      (node (ref "J5") (pin "D1") (pinfunction "D1_D1") (pintype "bidirectional"))
      (node (ref "J5") (pin "D2") (pinfunction "D2_D2") (pintype "bidirectional"))
      (node (ref "J6") (pin "2") (pinfunction "2_2") (pintype "bidirectional"))
    )
    (net (code "169") (name "P3V3_SOM_PL") (class "Default")
      (node (ref "C76") (pin "2") (pinfunction "2_2") (pintype "passive"))
      (node (ref "C77") (pin "2") (pinfunction "2_2") (pintype "passive"))
      (node (ref "J5") (pin "B13") (pinfunction "B13_B13") (pintype "bidirectional"))
      (node (ref "J5") (pin "B14") (pinfunction "B14_B14") (pintype "bidirectional"))
    )
    (net (code "170") (name "P5V0_SOM") (class "Default")
      (node (ref "C70") (pin "2") (pinfunction "2_2") (pintype "passive"))
      (node (ref "C71") (pin "2") (pinfunction "2_2") (pintype "passive"))
      (node (ref "C72") (pin "2") (pinfunction "2_2") (pintype "passive"))
      (node (ref "C73") (pin "2") (pinfunction "2_2") (pintype "passive"))
      (node (ref "C74") (pin "2") (pinfunction "2_2") (pintype "passive"))
      (node (ref "C75") (pin "2") (pinfunction "2_2") (pintype "passive"))
      (node (ref "J5") (pin "A59") (pinfunction "A59_A59") (pintype "bidirectional"))
      (node (ref "J5") (pin "A60") (pinfunction "A60_A60") (pintype "bidirectional"))
      (node (ref "J5") (pin "B60") (pinfunction "B60_B60") (pintype "bidirectional"))
      (node (ref "J5") (pin "C59") (pinfunction "C59_C59") (pintype "bidirectional"))
      (node (ref "J5") (pin "C60") (pinfunction "C60_C60") (pintype "bidirectional"))
      (node (ref "J5") (pin "D60") (pinfunction "D60_D60") (pintype "bidirectional"))
    )
    (net (code "171") (name "VBATT_SOM") (class "Default")
      (node (ref "J5") (pin "A1") (pinfunction "A1_A1") (pintype "bidirectional"))
      (node (ref "R114") (pin "1") (pinfunction "1_1") (pintype "passive"))
    )
    (net (code "172") (name "unconnected-(J6-Pad12)") (class "Default")
      (node (ref "J6") (pin "12") (pinfunction "12_12") (pintype "bidirectional+no_connect"))
    )
  )
)
